# USB2Power.net
KiCad netlist of a schematic drawn in EAGLE
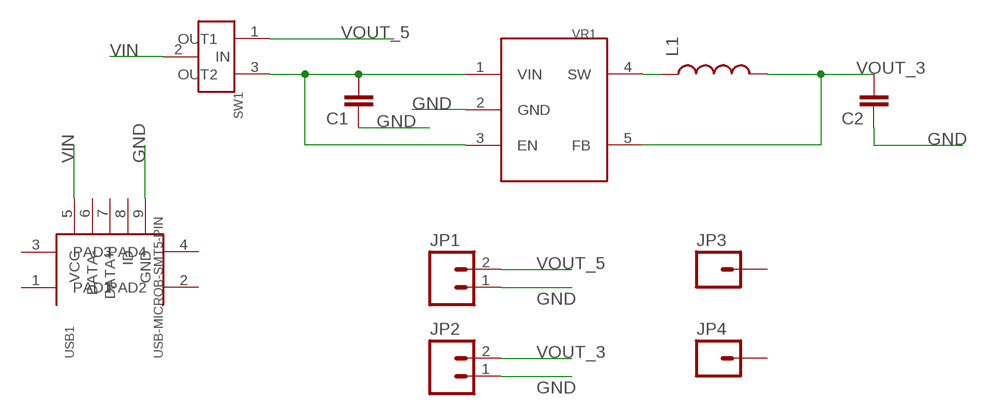
[diagram p0: schematic, sheet 1]

(export (version "E")
  (design (tool "Eeschema 10.0.6"))
  (components
    (comp (ref "C1")
      (value "CAP0603-CAP")
      (footprint "eagle-import:0603-CAP")
      (libsource (lib "eagle-import") (part "CAP0603-CAP"))
    )
    (comp (ref "C2")
      (value "CAP0603-CAP")
      (footprint "eagle-import:0603-CAP")
      (libsource (lib "eagle-import") (part "CAP0603-CAP"))
    )
    (comp (ref "JP1")
      (value "M02PTH")
      (footprint "eagle-import:1X02")
      (libsource (lib "eagle-import") (part "M02PTH"))
    )
    (comp (ref "JP2")
      (value "M02PTH")
      (footprint "eagle-import:1X02")
      (libsource (lib "eagle-import") (part "M02PTH"))
    )
    (comp (ref "JP3")
      (value "M01PTH")
      (footprint "eagle-import:1X01")
      (libsource (lib "eagle-import") (part "M01PTH"))
    )
    (comp (ref "JP4")
      (value "M01PTH")
      (footprint "eagle-import:1X01")
      (libsource (lib "eagle-import") (part "M01PTH"))
    )
    (comp (ref "L1")
      (value "INDUCTOR30OHM,1.8A")
      (footprint "eagle-import:0603")
      (libsource (lib "eagle-import") (part "INDUCTOR30OHM,1.8A"))
    )
    (comp (ref "SW1")
      (value "PCM12SMTR")
      (footprint "eagle-import:PCM12SMTR")
      (libsource (lib "eagle-import") (part "PCM12SMTR"))
    )
    (comp (ref "USB1")
      (value "USB-MICROB-SMT5-PIN")
      (footprint "eagle-import:USB-MICROB-SMT")
      (libsource (lib "eagle-import") (part "USB-MICROB-SMT5-PIN"))
    )
    (comp (ref "VR1")
      (value "ADP2108")
      (footprint "eagle-import:UJ-5_TSOT")
      (libsource (lib "eagle-import") (part "ADP2108"))
    )
  )
  (nets
    (net (code "1") (name "/GND") (class "Default")
      (node (ref "C1") (pin "1") (pinfunction "1_1") (pintype "passive"))
      (node (ref "C2") (pin "1") (pinfunction "1_1") (pintype "passive"))
      (node (ref "JP1") (pin "1") (pinfunction "1_1") (pintype "passive"))
      (node (ref "JP2") (pin "1") (pinfunction "1_1") (pintype "passive"))
      (node (ref "USB1") (pin "9") (pinfunction "GND_9") (pintype "bidirectional"))
      (node (ref "VR1") (pin "2") (pinfunction "GND_2") (pintype "bidirectional"))
    )
    (net (code "2") (name "/VIN") (class "Default")
      (node (ref "SW1") (pin "2") (pinfunction "IN_2") (pintype "bidirectional"))
      (node (ref "USB1") (pin "5") (pinfunction "VCC_5") (pintype "bidirectional"))
    )
    (net (code "3") (name "/VOUT_3") (class "Default")
      (node (ref "C2") (pin "2") (pinfunction "2_2") (pintype "passive"))
      (node (ref "JP2") (pin "2") (pinfunction "2_2") (pintype "passive"))
      (node (ref "L1") (pin "2") (pinfunction "2_2") (pintype "passive"))
      (node (ref "VR1") (pin "5") (pinfunction "FB_5") (pintype "bidirectional"))
    )
    (net (code "4") (name "/VOUT_5") (class "Default")
      (node (ref "JP1") (pin "2") (pinfunction "2_2") (pintype "passive"))
      (node (ref "SW1") (pin "1") (pinfunction "OUT1_1") (pintype "bidirectional"))
    )
    (net (code "5") (name "Net-(SW1-OUT2)") (class "Default")
      (node (ref "C1") (pin "2") (pinfunction "2_2") (pintype "passive"))
      (node (ref "SW1") (pin "3") (pinfunction "OUT2_3") (pintype "bidirectional"))
      (node (ref "VR1") (pin "1") (pinfunction "VIN_1") (pintype "bidirectional"))
      (node (ref "VR1") (pin "3") (pinfunction "EN_3") (pintype "bidirectional"))
    )
    (net (code "6") (name "Net-(VR1-SW)") (class "Default")
      (node (ref "L1") (pin "1") (pinfunction "1_1") (pintype "passive"))
      (node (ref "VR1") (pin "4") (pinfunction "SW_4") (pintype "bidirectional"))
    )
    (net (code "7") (name "unconnected-(JP3-Pad1)") (class "Default")
      (node (ref "JP3") (pin "1") (pinfunction "1_1") (pintype "passive"))
    )
    (net (code "8") (name "unconnected-(JP4-Pad1)") (class "Default")
      (node (ref "JP4") (pin "1") (pinfunction "1_1") (pintype "passive"))
    )
    (net (code "9") (name "unconnected-(USB1-DATA+-Pad7)") (class "Default")
      (node (ref "USB1") (pin "7") (pinfunction "DATA+_7") (pintype "bidirectional"))
    )
    (net (code "10") (name "unconnected-(USB1-DATA--Pad6)") (class "Default")
      (node (ref "USB1") (pin "6") (pinfunction "DATA-_6") (pintype "bidirectional"))
    )
    (net (code "11") (name "unconnected-(USB1-ID-Pad8)") (class "Default")
      (node (ref "USB1") (pin "8") (pinfunction "ID_8") (pintype "bidirectional"))
    )
    (net (code "12") (name "unconnected-(USB1-PAD1-Pad1)") (class "Default")
      (node (ref "USB1") (pin "1") (pinfunction "PAD1_1") (pintype "no_connect"))
    )
    (net (code "13") (name "unconnected-(USB1-PAD2-Pad2)") (class "Default")
      (node (ref "USB1") (pin "2") (pinfunction "PAD2_2") (pintype "no_connect"))
    )
    (net (code "14") (name "unconnected-(USB1-PAD3-Pad3)") (class "Default")
      (node (ref "USB1") (pin "3") (pinfunction "PAD3_3") (pintype "no_connect"))
    )
    (net (code "15") (name "unconnected-(USB1-PAD4-Pad4)") (class "Default")
      (node (ref "USB1") (pin "4") (pinfunction "PAD4_4") (pintype "no_connect"))
    )
  )
)
